# DualStepperController.net
KiCad netlist of a schematic drawn in EAGLE
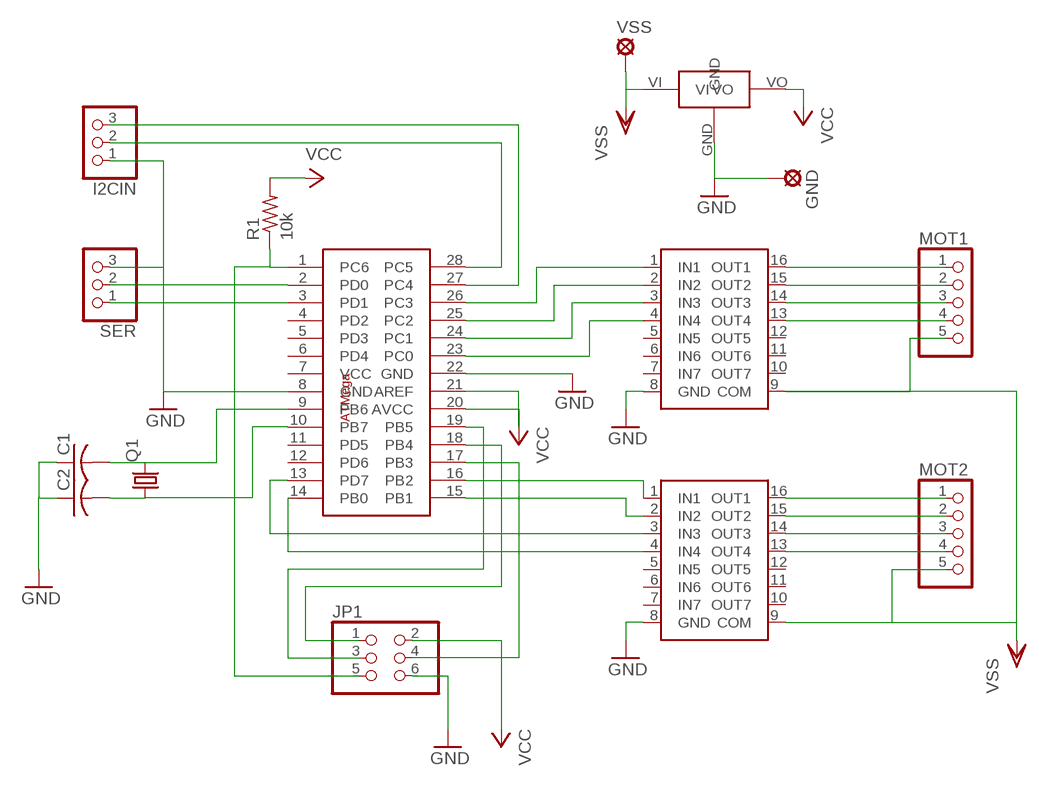
[diagram p0: schematic, sheet 1]

(export (version "E")
  (design (tool "Eeschema 10.0.6"))
  (components
    (comp (ref "C1")
      (value "C-US025-024X044")
      (footprint "eagle-import:C025-024X044")
      (libsource (lib "eagle-import") (part "C-US025-024X044"))
    )
    (comp (ref "C2")
      (value "C-US025-024X044")
      (footprint "eagle-import:C025-024X044")
      (libsource (lib "eagle-import") (part "C-US025-024X044"))
    )
    (comp (ref "GND")
      (value "SE14")
      (footprint "eagle-import:SE14")
      (libsource (lib "eagle-import") (part "SE14"))
    )
    (comp (ref "I2CIN")
      (value "PINHD-1X3")
      (footprint "eagle-import:1X03")
      (libsource (lib "eagle-import") (part "PINHD-1X3"))
    )
    (comp (ref "JP1")
      (value "PINHD-2X3")
      (footprint "eagle-import:2X03")
      (libsource (lib "eagle-import") (part "PINHD-2X3"))
    )
    (comp (ref "MOT1")
      (value "PINHD-1X5")
      (footprint "eagle-import:1X05")
      (libsource (lib "eagle-import") (part "PINHD-1X5"))
    )
    (comp (ref "MOT2")
      (value "PINHD-1X5")
      (footprint "eagle-import:1X05")
      (libsource (lib "eagle-import") (part "PINHD-1X5"))
    )
    (comp (ref "Q1")
      (value "CRYSTALHC49S")
      (footprint "eagle-import:HC49_S")
      (libsource (lib "eagle-import") (part "CRYSTALHC49S"))
    )
    (comp (ref "R1")
      (value "10k")
      (footprint "eagle-import:0207_7")
      (libsource (lib "eagle-import") (part "R-US_0207/7"))
    )
    (comp (ref "SER")
      (value "PINHD-1X3")
      (footprint "eagle-import:1X03")
      (libsource (lib "eagle-import") (part "PINHD-1X3"))
    )
    (comp (ref "U$1")
      (value "ATMEGA328P")
      (footprint "eagle-import:ATMEGA328P-DIP")
      (libsource (lib "eagle-import") (part "ATMEGA328P"))
    )
    (comp (ref "U$2")
      (value "ULN2003")
      (footprint "eagle-import:DIP16")
      (libsource (lib "eagle-import") (part "ULN2003"))
    )
    (comp (ref "U$3")
      (value "ULN2003")
      (footprint "eagle-import:DIP16")
      (libsource (lib "eagle-import") (part "ULN2003"))
    )
    (comp (ref "U$4")
      (value "7805-TO220V")
      (footprint "eagle-import:TO220AV")
      (libsource (lib "eagle-import") (part "7805-TO220V"))
    )
    (comp (ref "VSS")
      (value "SE14")
      (footprint "eagle-import:SE14")
      (libsource (lib "eagle-import") (part "SE14"))
    )
  )
  (nets
    (net (code "1") (name "GND") (class "Default")
      (node (ref "C1") (pin "1") (pinfunction "1_1") (pintype "passive"))
      (node (ref "C2") (pin "1") (pinfunction "1_1") (pintype "passive"))
      (node (ref "GND") (pin "MP") (pinfunction "MP_MP") (pintype "passive"))
      (node (ref "I2CIN") (pin "1") (pinfunction "1_1") (pintype "passive"))
      (node (ref "JP1") (pin "6") (pinfunction "6_6") (pintype "passive"))
      (node (ref "SER") (pin "3") (pinfunction "3_3") (pintype "passive"))
      (node (ref "U$1") (pin "22") (pinfunction "GND_22") (pintype "bidirectional"))
      (node (ref "U$1") (pin "8") (pinfunction "GND_8") (pintype "bidirectional"))
      (node (ref "U$2") (pin "8") (pinfunction "GND_8") (pintype "bidirectional"))
      (node (ref "U$3") (pin "8") (pinfunction "GND_8") (pintype "bidirectional"))
      (node (ref "U$4") (pin "GND") (pinfunction "GND_GND") (pintype "bidirectional"))
    )
    (net (code "2") (name "Net-(U$1-PB0)") (class "Default")
      (node (ref "U$1") (pin "14") (pinfunction "PB0_14") (pintype "bidirectional"))
      (node (ref "U$3") (pin "4") (pinfunction "IN4_4") (pintype "bidirectional"))
    )
    (net (code "3") (name "Net-(U$1-PB1)") (class "Default")
      (node (ref "U$1") (pin "15") (pinfunction "PB1_15") (pintype "bidirectional"))
      (node (ref "U$3") (pin "2") (pinfunction "IN2_2") (pintype "bidirectional"))
    )
    (net (code "4") (name "Net-(U$1-PB2)") (class "Default")
      (node (ref "U$1") (pin "16") (pinfunction "PB2_16") (pintype "bidirectional"))
      (node (ref "U$3") (pin "1") (pinfunction "IN1_1") (pintype "bidirectional"))
    )
    (net (code "5") (name "Net-(U$1-PB3)") (class "Default")
      (node (ref "JP1") (pin "4") (pinfunction "4_4") (pintype "passive"))
      (node (ref "U$1") (pin "17") (pinfunction "PB3_17") (pintype "bidirectional"))
    )
    (net (code "6") (name "Net-(U$1-PB4)") (class "Default")
      (node (ref "JP1") (pin "1") (pinfunction "1_1") (pintype "passive"))
      (node (ref "U$1") (pin "18") (pinfunction "PB4_18") (pintype "bidirectional"))
    )
    (net (code "7") (name "Net-(U$1-PB5)") (class "Default")
      (node (ref "JP1") (pin "3") (pinfunction "3_3") (pintype "passive"))
      (node (ref "U$1") (pin "19") (pinfunction "PB5_19") (pintype "bidirectional"))
    )
    (net (code "8") (name "Net-(U$1-PB6)") (class "Default")
      (node (ref "C1") (pin "2") (pinfunction "2_2") (pintype "passive"))
      (node (ref "Q1") (pin "2") (pinfunction "2_2") (pintype "passive"))
      (node (ref "U$1") (pin "9") (pinfunction "PB6_9") (pintype "bidirectional"))
    )
    (net (code "9") (name "Net-(U$1-PB7)") (class "Default")
      (node (ref "C2") (pin "2") (pinfunction "2_2") (pintype "passive"))
      (node (ref "Q1") (pin "1") (pinfunction "1_1") (pintype "passive"))
      (node (ref "U$1") (pin "10") (pinfunction "PB7_10") (pintype "bidirectional"))
    )
    (net (code "10") (name "Net-(U$1-PC0)") (class "Default")
      (node (ref "U$1") (pin "23") (pinfunction "PC0_23") (pintype "bidirectional"))
      (node (ref "U$2") (pin "4") (pinfunction "IN4_4") (pintype "bidirectional"))
    )
    (net (code "11") (name "Net-(U$1-PC1)") (class "Default")
      (node (ref "U$1") (pin "24") (pinfunction "PC1_24") (pintype "bidirectional"))
      (node (ref "U$2") (pin "3") (pinfunction "IN3_3") (pintype "bidirectional"))
    )
    (net (code "12") (name "Net-(U$1-PC2)") (class "Default")
      (node (ref "U$1") (pin "25") (pinfunction "PC2_25") (pintype "bidirectional"))
      (node (ref "U$2") (pin "2") (pinfunction "IN2_2") (pintype "bidirectional"))
    )
    (net (code "13") (name "Net-(U$1-PC3)") (class "Default")
      (node (ref "U$1") (pin "26") (pinfunction "PC3_26") (pintype "bidirectional"))
      (node (ref "U$2") (pin "1") (pinfunction "IN1_1") (pintype "bidirectional"))
    )
    (net (code "14") (name "Net-(U$1-PC4)") (class "Default")
      (node (ref "I2CIN") (pin "3") (pinfunction "3_3") (pintype "passive"))
      (node (ref "U$1") (pin "27") (pinfunction "PC4_27") (pintype "bidirectional"))
    )
    (net (code "15") (name "Net-(U$1-PC5)") (class "Default")
      (node (ref "I2CIN") (pin "2") (pinfunction "2_2") (pintype "passive"))
      (node (ref "U$1") (pin "28") (pinfunction "PC5_28") (pintype "bidirectional"))
    )
    (net (code "16") (name "Net-(U$1-PC6)") (class "Default")
      (node (ref "JP1") (pin "5") (pinfunction "5_5") (pintype "passive"))
      (node (ref "R1") (pin "1") (pinfunction "1_1") (pintype "passive"))
      (node (ref "U$1") (pin "1") (pinfunction "PC6_1") (pintype "bidirectional"))
    )
    (net (code "17") (name "Net-(U$1-PD0)") (class "Default")
      (node (ref "SER") (pin "2") (pinfunction "2_2") (pintype "passive"))
      (node (ref "U$1") (pin "2") (pinfunction "PD0_2") (pintype "bidirectional"))
    )
    (net (code "18") (name "Net-(U$1-PD1)") (class "Default")
      (node (ref "SER") (pin "1") (pinfunction "1_1") (pintype "passive"))
      (node (ref "U$1") (pin "3") (pinfunction "PD1_3") (pintype "bidirectional"))
    )
    (net (code "19") (name "Net-(U$1-PD7)") (class "Default")
      (node (ref "U$1") (pin "13") (pinfunction "PD7_13") (pintype "bidirectional"))
      (node (ref "U$3") (pin "3") (pinfunction "IN3_3") (pintype "bidirectional"))
    )
    (net (code "20") (name "Net-(U$2-OUT1)") (class "Default")
      (node (ref "MOT1") (pin "1") (pinfunction "1_1") (pintype "passive"))
      (node (ref "U$2") (pin "16") (pinfunction "OUT1_16") (pintype "bidirectional"))
    )
    (net (code "21") (name "Net-(U$2-OUT2)") (class "Default")
      (node (ref "MOT1") (pin "2") (pinfunction "2_2") (pintype "passive"))
      (node (ref "U$2") (pin "15") (pinfunction "OUT2_15") (pintype "bidirectional"))
    )
    (net (code "22") (name "Net-(U$2-OUT3)") (class "Default")
      (node (ref "MOT1") (pin "3") (pinfunction "3_3") (pintype "passive"))
      (node (ref "U$2") (pin "14") (pinfunction "OUT3_14") (pintype "bidirectional"))
    )
    (net (code "23") (name "Net-(U$2-OUT4)") (class "Default")
      (node (ref "MOT1") (pin "4") (pinfunction "4_4") (pintype "passive"))
      (node (ref "U$2") (pin "13") (pinfunction "OUT4_13") (pintype "bidirectional"))
    )
    (net (code "24") (name "Net-(U$3-OUT1)") (class "Default")
      (node (ref "MOT2") (pin "1") (pinfunction "1_1") (pintype "passive"))
      (node (ref "U$3") (pin "16") (pinfunction "OUT1_16") (pintype "bidirectional"))
    )
    (net (code "25") (name "Net-(U$3-OUT2)") (class "Default")
      (node (ref "MOT2") (pin "2") (pinfunction "2_2") (pintype "passive"))
      (node (ref "U$3") (pin "15") (pinfunction "OUT2_15") (pintype "bidirectional"))
    )
    (net (code "26") (name "Net-(U$3-OUT3)") (class "Default")
      (node (ref "MOT2") (pin "3") (pinfunction "3_3") (pintype "passive"))
      (node (ref "U$3") (pin "14") (pinfunction "OUT3_14") (pintype "bidirectional"))
    )
    (net (code "27") (name "Net-(U$3-OUT4)") (class "Default")
      (node (ref "MOT2") (pin "4") (pinfunction "4_4") (pintype "passive"))
      (node (ref "U$3") (pin "13") (pinfunction "OUT4_13") (pintype "bidirectional"))
    )
    (net (code "28") (name "VCC") (class "Default")
      (node (ref "JP1") (pin "2") (pinfunction "2_2") (pintype "passive"))
      (node (ref "R1") (pin "2") (pinfunction "2_2") (pintype "passive"))
      (node (ref "U$1") (pin "20") (pinfunction "AVCC_20") (pintype "bidirectional"))
      (node (ref "U$1") (pin "21") (pinfunction "AREF_21") (pintype "bidirectional"))
      (node (ref "U$4") (pin "VO") (pinfunction "VO_VO") (pintype "output"))
    )
    (net (code "29") (name "VSS") (class "Default")
      (node (ref "MOT1") (pin "5") (pinfunction "5_5") (pintype "passive"))
      (node (ref "MOT2") (pin "5") (pinfunction "5_5") (pintype "passive"))
      (node (ref "U$2") (pin "9") (pinfunction "COM_9") (pintype "bidirectional"))
      (node (ref "U$3") (pin "9") (pinfunction "COM_9") (pintype "bidirectional"))
      (node (ref "U$4") (pin "VI") (pinfunction "VI_VI") (pintype "input"))
      (node (ref "VSS") (pin "MP") (pinfunction "MP_MP") (pintype "passive"))
    )
    (net (code "30") (name "unconnected-(U$1-PD2-Pad4)") (class "Default")
      (node (ref "U$1") (pin "4") (pinfunction "PD2_4") (pintype "bidirectional"))
    )
    (net (code "31") (name "unconnected-(U$1-PD3-Pad5)") (class "Default")
      (node (ref "U$1") (pin "5") (pinfunction "PD3_5") (pintype "bidirectional"))
    )
    (net (code "32") (name "unconnected-(U$1-PD4-Pad6)") (class "Default")
      (node (ref "U$1") (pin "6") (pinfunction "PD4_6") (pintype "bidirectional"))
    )
    (net (code "33") (name "unconnected-(U$1-PD5-Pad11)") (class "Default")
      (node (ref "U$1") (pin "11") (pinfunction "PD5_11") (pintype "bidirectional"))
    )
    (net (code "34") (name "unconnected-(U$1-PD6-Pad12)") (class "Default")
      (node (ref "U$1") (pin "12") (pinfunction "PD6_12") (pintype "bidirectional"))
    )
    (net (code "35") (name "unconnected-(U$1-VCC-Pad7)") (class "Default")
      (node (ref "U$1") (pin "7") (pinfunction "VCC_7") (pintype "bidirectional"))
    )
    (net (code "36") (name "unconnected-(U$2-IN5-Pad5)") (class "Default")
      (node (ref "U$2") (pin "5") (pinfunction "IN5_5") (pintype "bidirectional"))
    )
    (net (code "37") (name "unconnected-(U$2-IN6-Pad6)") (class "Default")
      (node (ref "U$2") (pin "6") (pinfunction "IN6_6") (pintype "bidirectional"))
    )
    (net (code "38") (name "unconnected-(U$2-IN7-Pad7)") (class "Default")
      (node (ref "U$2") (pin "7") (pinfunction "IN7_7") (pintype "bidirectional"))
    )
    (net (code "39") (name "unconnected-(U$2-OUT5-Pad12)") (class "Default")
      (node (ref "U$2") (pin "12") (pinfunction "OUT5_12") (pintype "bidirectional"))
    )
    (net (code "40") (name "unconnected-(U$2-OUT6-Pad11)") (class "Default")
      (node (ref "U$2") (pin "11") (pinfunction "OUT6_11") (pintype "bidirectional"))
    )
    (net (code "41") (name "unconnected-(U$2-OUT7-Pad10)") (class "Default")
      (node (ref "U$2") (pin "10") (pinfunction "OUT7_10") (pintype "bidirectional"))
    )
    (net (code "42") (name "unconnected-(U$3-IN5-Pad5)") (class "Default")
      (node (ref "U$3") (pin "5") (pinfunction "IN5_5") (pintype "bidirectional"))
    )
    (net (code "43") (name "unconnected-(U$3-IN6-Pad6)") (class "Default")
      (node (ref "U$3") (pin "6") (pinfunction "IN6_6") (pintype "bidirectional"))
    )
    (net (code "44") (name "unconnected-(U$3-IN7-Pad7)") (class "Default")
      (node (ref "U$3") (pin "7") (pinfunction "IN7_7") (pintype "bidirectional"))
    )
    (net (code "45") (name "unconnected-(U$3-OUT5-Pad12)") (class "Default")
      (node (ref "U$3") (pin "12") (pinfunction "OUT5_12") (pintype "bidirectional"))
    )
    (net (code "46") (name "unconnected-(U$3-OUT6-Pad11)") (class "Default")
      (node (ref "U$3") (pin "11") (pinfunction "OUT6_11") (pintype "bidirectional"))
    )
    (net (code "47") (name "unconnected-(U$3-OUT7-Pad10)") (class "Default")
      (node (ref "U$3") (pin "10") (pinfunction "OUT7_10") (pintype "bidirectional"))
    )
  )
)
